# npn_switch.net
KiCad netlist of a schematic drawn in EAGLE
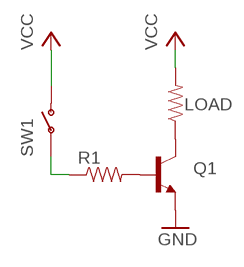
[diagram p0: schematic, sheet 1]

(export (version "E")
  (design (tool "Eeschema 10.0.6"))
  (components
    (comp (ref "LOAD")
      (value "RESISTOR")
      (footprint "eagle-import:0603RES")
      (libsource (lib "eagle-import") (part "RESISTOR"))
    )
    (comp (ref "Q1")
      (value "TRANSISTOR_NPN\"")
      (footprint "eagle-import:SOT223")
      (libsource (lib "eagle-import") (part "TRANSISTOR_NPN{dblquote}"))
    )
    (comp (ref "R1")
      (value "RESISTOR")
      (footprint "eagle-import:0603RES")
      (libsource (lib "eagle-import") (part "RESISTOR"))
    )
    (comp (ref "SW1")
      (value "SWITCH-SPST-2RA")
      (footprint "eagle-import:R_SW_TH")
      (libsource (lib "eagle-import") (part "SWITCH-SPST-2RA"))
    )
  )
  (nets
    (net (code "1") (name "GND") (class "Default")
      (node (ref "Q1") (pin "3") (pinfunction "E_3") (pintype "passive"))
    )
    (net (code "2") (name "Net-(Q1-B)") (class "Default")
      (node (ref "Q1") (pin "1") (pinfunction "B_1") (pintype "passive"))
      (node (ref "R1") (pin "2") (pinfunction "2_2") (pintype "passive"))
    )
    (net (code "3") (name "Net-(Q1-C)") (class "Default")
      (node (ref "LOAD") (pin "1") (pinfunction "1_1") (pintype "passive"))
      (node (ref "Q1") (pin "2") (pinfunction "C_2") (pintype "passive"))
    )
    (net (code "4") (name "Net-(SW1-P)") (class "Default")
      (node (ref "R1") (pin "1") (pinfunction "1_1") (pintype "passive"))
      (node (ref "SW1") (pin "P$4") (pinfunction "P_P$4") (pintype "passive"))
    )
    (net (code "5") (name "VCC") (class "Default")
      (node (ref "LOAD") (pin "2") (pinfunction "2_2") (pintype "passive"))
      (node (ref "SW1") (pin "P$3") (pinfunction "O_P$3") (pintype "passive"))
    )
  )
)
